# 3K_valdiklis_v1.net
KiCad netlist of a schematic drawn in EAGLE
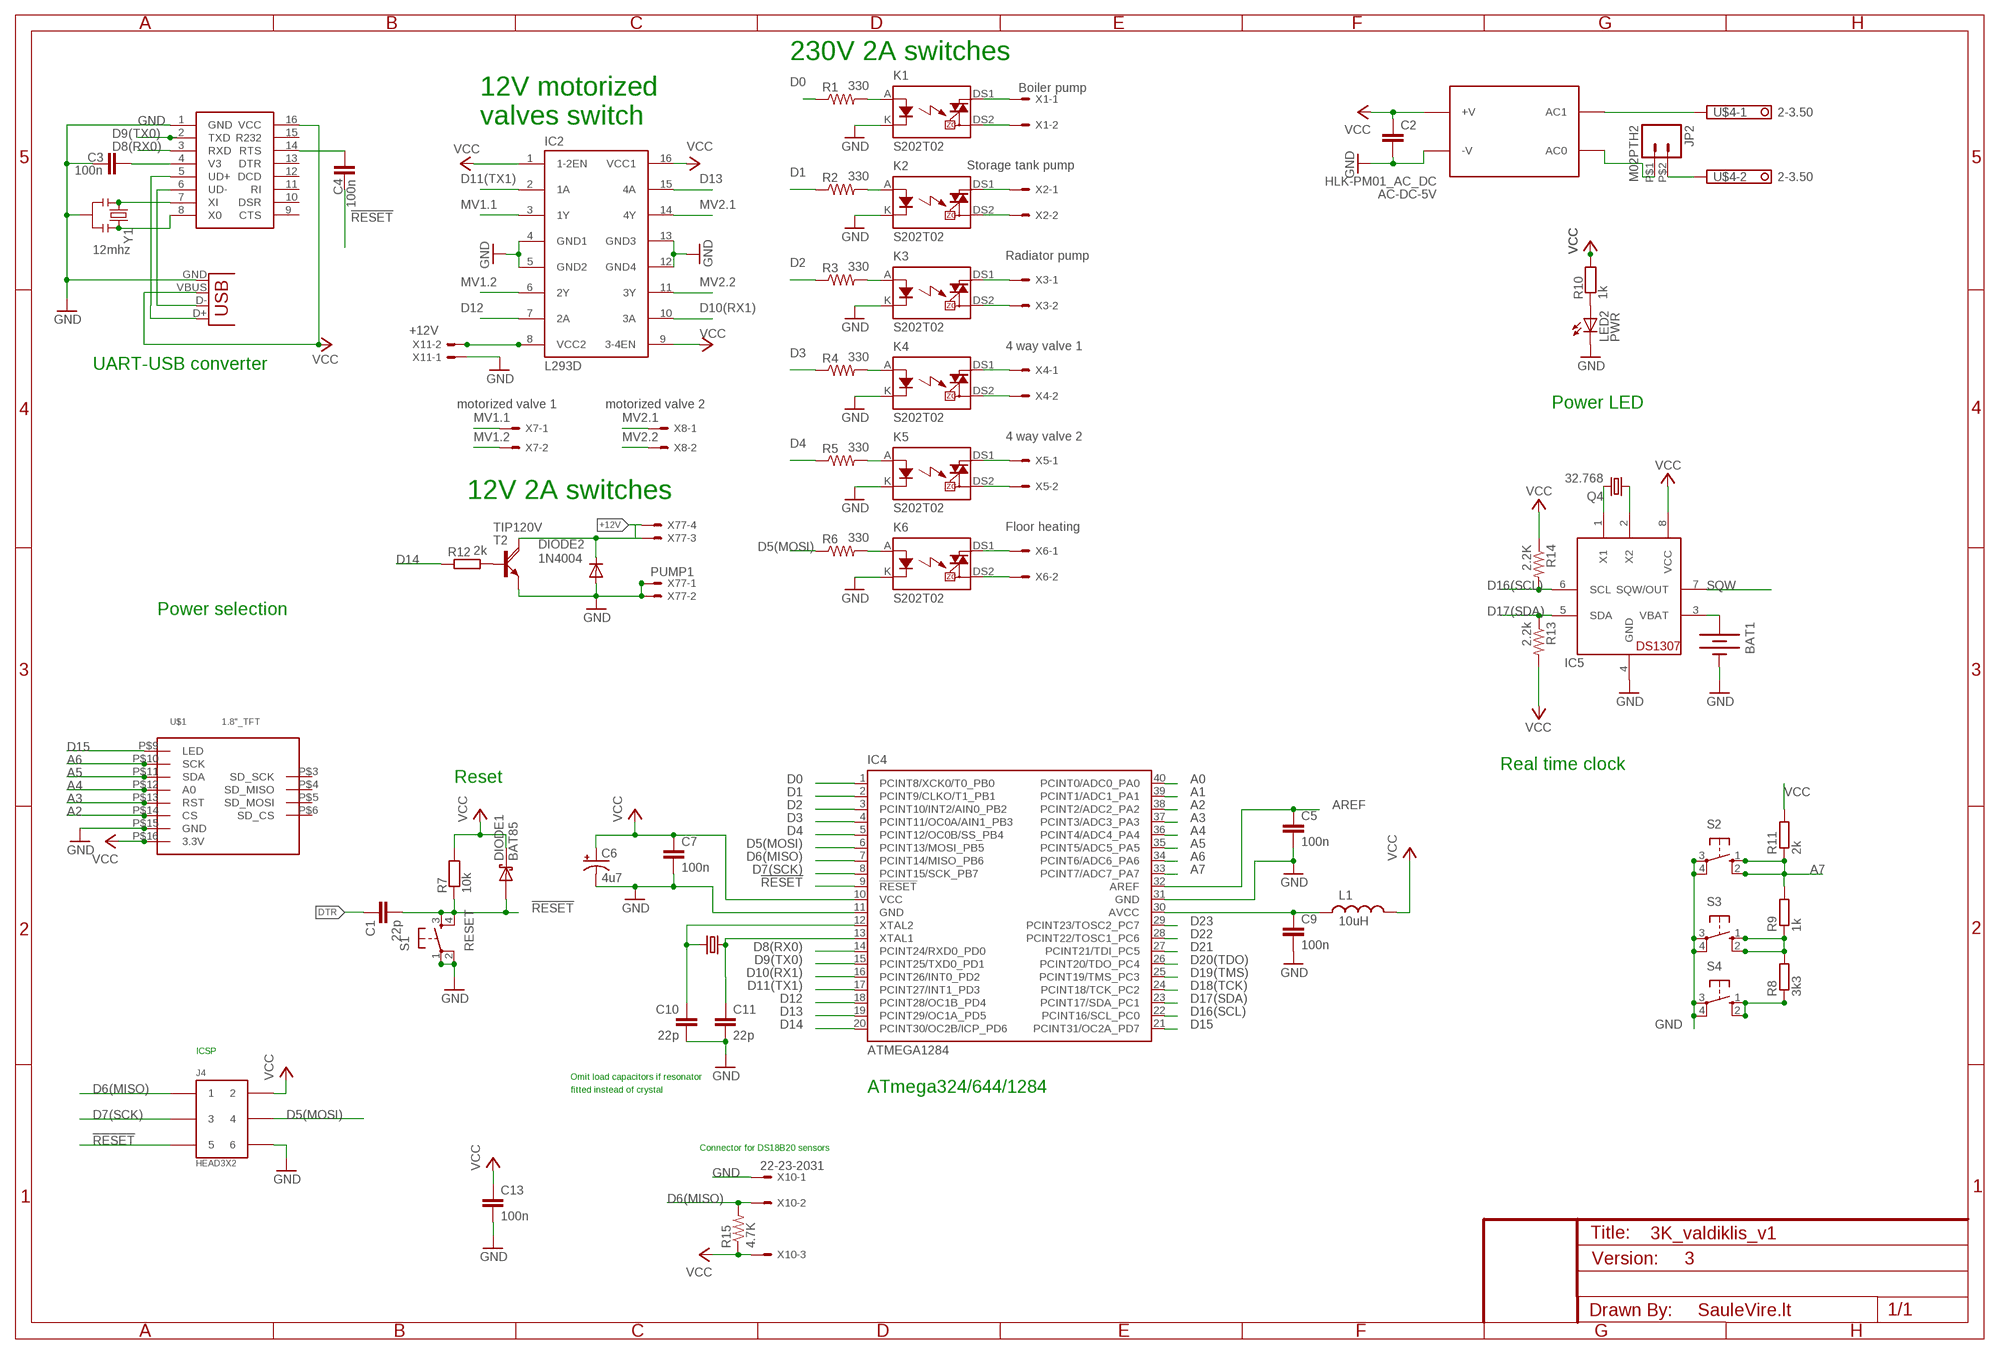
[diagram p0: schematic, sheet 1]

(export (version "E")
  (design (tool "Eeschema 10.0.6"))
  (components
    (comp (ref "AC-DC-5V")
      (value "HLK-PM01_AC_DC")
      (footprint "eagle-import:HLK-PM01_AC_DC")
      (libsource (lib "eagle-import") (part "HLK-PM01_AC_DC"))
    )
    (comp (ref "BAT1")
      (value "BATTERY20PTH")
      (footprint "eagle-import:BATTCOM_20MM_PTH")
      (libsource (lib "eagle-import") (part "BATTERY20PTH"))
    )
    (comp (ref "C1")
      (value "22p")
      (footprint "eagle-import:CAP-PTH-SMALL")
      (libsource (lib "eagle-import") (part "CAPPTH"))
    )
    (comp (ref "C2")
      (value "C-EU025-024X044")
      (footprint "eagle-import:C025-024X044")
      (libsource (lib "eagle-import") (part "C-EU025-024X044"))
    )
    (comp (ref "C3")
      (value "100n")
      (footprint "eagle-import:CAP-PTH-SMALL")
      (libsource (lib "eagle-import") (part "CAPPTH"))
    )
    (comp (ref "C4")
      (value "100n")
      (footprint "eagle-import:CAP-PTH-SMALL")
      (libsource (lib "eagle-import") (part "CAPPTH"))
    )
    (comp (ref "C5")
      (value "100n")
      (footprint "eagle-import:CAP-PTH-SMALL")
      (libsource (lib "eagle-import") (part "CAPPTH"))
    )
    (comp (ref "C6")
      (value "4u7")
      (footprint "eagle-import:CPOL-RADIAL-10UF-25V")
      (libsource (lib "eagle-import") (part "CAP_POLPTH2"))
    )
    (comp (ref "C7")
      (value "100n")
      (footprint "eagle-import:CAP-PTH-SMALL")
      (libsource (lib "eagle-import") (part "CAPPTH"))
    )
    (comp (ref "C9")
      (value "100n")
      (footprint "eagle-import:CAP-PTH-SMALL")
      (libsource (lib "eagle-import") (part "CAPPTH"))
    )
    (comp (ref "C10")
      (value "22p")
      (footprint "eagle-import:CAP-PTH-SMALL")
      (libsource (lib "eagle-import") (part "CAPPTH"))
    )
    (comp (ref "C11")
      (value "22p")
      (footprint "eagle-import:CAP-PTH-SMALL")
      (libsource (lib "eagle-import") (part "CAPPTH"))
    )
    (comp (ref "C13")
      (value "100n")
      (footprint "eagle-import:CAP-PTH-SMALL")
      (libsource (lib "eagle-import") (part "CAPPTH"))
    )
    (comp (ref "DIODE1")
      (value "BAT85")
      (footprint "eagle-import:DIODE-TH-0.4")
      (libsource (lib "eagle-import") (part "DIODE-SCHOTTKY"))
    )
    (comp (ref "DIODE2")
      (value "1N4004")
      (footprint "eagle-import:DO41-10")
      (libsource (lib "eagle-import") (part "1N4004"))
    )
    (comp (ref "IC2")
      (value "L293D")
      (footprint "eagle-import:DIL16")
      (libsource (lib "eagle-import") (part "L293D"))
    )
    (comp (ref "IC4")
      (value "ATMEGA1284")
      (footprint "eagle-import:DIL40")
      (fields (field (name "MPN") "ATMEGA644-20PU"))
      (libsource (lib "eagle-import") (part "ATMEGA644-PU20"))
    )
    (comp (ref "IC5")
      (value "DS1307")
      (footprint "eagle-import:DIL08")
      (libsource (lib "eagle-import") (part "DS1307"))
    )
    (comp (ref "J4")
      (value "HEAD3X2")
      (footprint "eagle-import:HEAD3X2")
      (libsource (lib "eagle-import") (part "HEAD3X2"))
    )
    (comp (ref "JP2")
      (value "M02PTH2")
      (footprint "eagle-import:1X02_BIG")
      (libsource (lib "eagle-import") (part "M02PTH2"))
    )
    (comp (ref "JP3")
      (value "USB-B")
      (footprint "eagle-import:USB-B-PTH")
      (libsource (lib "eagle-import") (part "USBPTH"))
    )
    (comp (ref "K1")
      (value "S202T02")
      (footprint "eagle-import:S202T02")
      (libsource (lib "eagle-import") (part "S202T02"))
    )
    (comp (ref "K2")
      (value "S202T02")
      (footprint "eagle-import:S202T02")
      (libsource (lib "eagle-import") (part "S202T02"))
    )
    (comp (ref "K3")
      (value "S202T02")
      (footprint "eagle-import:S202T02")
      (libsource (lib "eagle-import") (part "S202T02"))
    )
    (comp (ref "K4")
      (value "S202T02")
      (footprint "eagle-import:S202T02")
      (libsource (lib "eagle-import") (part "S202T02"))
    )
    (comp (ref "K5")
      (value "S202T02")
      (footprint "eagle-import:S202T02")
      (libsource (lib "eagle-import") (part "S202T02"))
    )
    (comp (ref "K6")
      (value "S202T02")
      (footprint "eagle-import:S202T02")
      (libsource (lib "eagle-import") (part "S202T02"))
    )
    (comp (ref "L1")
      (value "10uH")
      (footprint "eagle-import:RES-AXIAL-0.4")
      (libsource (lib "eagle-import") (part "INDUCTOR0.4{dblquote}-AXIAL"))
    )
    (comp (ref "LED2")
      (value "PWR")
      (footprint "eagle-import:LED3MM")
      (libsource (lib "eagle-import") (part "LED3MM"))
    )
    (comp (ref "Q4")
      (value "32.768")
      (footprint "eagle-import:TC38H")
      (libsource (lib "eagle-import") (part "CRYTALTC38H"))
    )
    (comp (ref "R1")
      (value "330")
      (footprint "eagle-import:0207_10")
      (libsource (lib "eagle-import") (part "resistor-1_R-US_0207/10"))
    )
    (comp (ref "R2")
      (value "330")
      (footprint "eagle-import:0207_10")
      (libsource (lib "eagle-import") (part "resistor-1_R-US_0207/10"))
    )
    (comp (ref "R3")
      (value "330")
      (footprint "eagle-import:0207_10")
      (libsource (lib "eagle-import") (part "resistor-1_R-US_0207/10"))
    )
    (comp (ref "R4")
      (value "330")
      (footprint "eagle-import:0207_10")
      (libsource (lib "eagle-import") (part "resistor-1_R-US_0207/10"))
    )
    (comp (ref "R5")
      (value "330")
      (footprint "eagle-import:0207_10")
      (libsource (lib "eagle-import") (part "resistor-1_R-US_0207/10"))
    )
    (comp (ref "R6")
      (value "330")
      (footprint "eagle-import:0207_10")
      (libsource (lib "eagle-import") (part "resistor-1_R-US_0207/10"))
    )
    (comp (ref "R7")
      (value "10k")
      (footprint "eagle-import:RES-AXIAL-0.4")
      (libsource (lib "eagle-import") (part "RESISTOR"))
    )
    (comp (ref "R8")
      (value "3k3")
      (footprint "eagle-import:0207_10")
      (libsource (lib "eagle-import") (part "R-EU_0207/10"))
    )
    (comp (ref "R9")
      (value "1k")
      (footprint "eagle-import:0207_10")
      (libsource (lib "eagle-import") (part "R-EU_0207/10"))
    )
    (comp (ref "R10")
      (value "1k")
      (footprint "eagle-import:RES-AXIAL-0.4")
      (libsource (lib "eagle-import") (part "RESISTOR"))
    )
    (comp (ref "R11")
      (value "2k")
      (footprint "eagle-import:0207_10")
      (libsource (lib "eagle-import") (part "R-EU_0207/10"))
    )
    (comp (ref "R12")
      (value "2k")
      (footprint "eagle-import:0207_10")
      (libsource (lib "eagle-import") (part "R-EU_0207/10"))
    )
    (comp (ref "R13")
      (value "2.2k")
      (footprint "eagle-import:0207_10")
      (libsource (lib "eagle-import") (part "R-US_0207/10"))
    )
    (comp (ref "R14")
      (value "2.2K")
      (footprint "eagle-import:0207_10")
      (libsource (lib "eagle-import") (part "R-US_0207/10"))
    )
    (comp (ref "R15")
      (value "4.7K")
      (footprint "eagle-import:0207_10")
      (libsource (lib "eagle-import") (part "R-US_0207/10"))
    )
    (comp (ref "S1")
      (value "RESET")
      (footprint "eagle-import:TACTILE-PTH")
      (libsource (lib "eagle-import") (part "TAC_SWITCHPTH"))
    )
    (comp (ref "S2")
      (value "10-XX")
      (footprint "eagle-import:B3F-10XX")
      (fields (field (name "MPN") "B3F-1000"))
      (libsource (lib "eagle-import") (part "10-XX"))
    )
    (comp (ref "S3")
      (value "10-XX")
      (footprint "eagle-import:B3F-10XX")
      (fields (field (name "MPN") "B3F-1000"))
      (libsource (lib "eagle-import") (part "10-XX"))
    )
    (comp (ref "S4")
      (value "10-XX")
      (footprint "eagle-import:B3F-10XX")
      (fields (field (name "MPN") "B3F-1000"))
      (libsource (lib "eagle-import") (part "10-XX"))
    )
    (comp (ref "T2")
      (value "TIP120V")
      (footprint "eagle-import:TO220AV")
      (libsource (lib "eagle-import") (part "TIP120V"))
    )
    (comp (ref "U$1")
      (value "1.8\"_TFT")
      (footprint "eagle-import:1.8__TFT")
      (libsource (lib "eagle-import") (part "1.8{dblquote}_TFT"))
    )
    (comp (ref "U$2")
      (value "CH340G")
      (footprint "eagle-import:SO016")
      (libsource (lib "eagle-import") (part "CH340G"))
    )
    (comp (ref "U$4")
      (value "2-3.50")
      (footprint "eagle-import:2-3.50")
      (libsource (lib "eagle-import") (part "2-3.50"))
    )
    (comp (ref "X1")
      (value "Boiler pump")
      (footprint "eagle-import:22-23-2021")
      (fields (field (name "MF") "MOLEX") (field (name "MPN") "22-23-2021"))
      (libsource (lib "eagle-import") (part "22-23-2021"))
    )
    (comp (ref "X2")
      (value "Storage tank pump")
      (footprint "eagle-import:22-23-2021")
      (fields (field (name "MF") "MOLEX") (field (name "MPN") "22-23-2021"))
      (libsource (lib "eagle-import") (part "22-23-2021"))
    )
    (comp (ref "X3")
      (value "Radiator pump")
      (footprint "eagle-import:22-23-2021")
      (fields (field (name "MF") "MOLEX") (field (name "MPN") "22-23-2021"))
      (libsource (lib "eagle-import") (part "22-23-2021"))
    )
    (comp (ref "X4")
      (value "4 way valve 1")
      (footprint "eagle-import:22-23-2021")
      (fields (field (name "MF") "MOLEX") (field (name "MPN") "22-23-2021"))
      (libsource (lib "eagle-import") (part "22-23-2021"))
    )
    (comp (ref "X5")
      (value "4 way valve 2")
      (footprint "eagle-import:22-23-2021")
      (fields (field (name "MF") "MOLEX") (field (name "MPN") "22-23-2021"))
      (libsource (lib "eagle-import") (part "22-23-2021"))
    )
    (comp (ref "X6")
      (value "Floor heating")
      (footprint "eagle-import:22-23-2021")
      (fields (field (name "MF") "MOLEX") (field (name "MPN") "22-23-2021"))
      (libsource (lib "eagle-import") (part "22-23-2021"))
    )
    (comp (ref "X7")
      (value "motorized valve 1")
      (footprint "eagle-import:22-23-2021")
      (fields (field (name "MF") "MOLEX") (field (name "MPN") "22-23-2021"))
      (libsource (lib "eagle-import") (part "22-23-2021"))
    )
    (comp (ref "X8")
      (value "motorized valve 2")
      (footprint "eagle-import:22-23-2021")
      (fields (field (name "MF") "MOLEX") (field (name "MPN") "22-23-2021"))
      (libsource (lib "eagle-import") (part "22-23-2021"))
    )
    (comp (ref "X9")
      (value "16MHz")
      (footprint "eagle-import:HC49US")
      (libsource (lib "eagle-import") (part "CRYSTALHC49US"))
    )
    (comp (ref "X10")
      (value "22-23-2031")
      (footprint "eagle-import:22-23-2031")
      (fields (field (name "MF") "MOLEX"))
      (libsource (lib "eagle-import") (part "22-23-2031"))
    )
    (comp (ref "X11")
      (value "+12V")
      (footprint "eagle-import:22-23-2021")
      (fields (field (name "MF") "MOLEX") (field (name "MPN") "22-23-2021"))
      (libsource (lib "eagle-import") (part "22-23-2021"))
    )
    (comp (ref "X77")
      (value "PUMP1")
      (footprint "eagle-import:22-23-2041")
      (fields (field (name "MF") "MOLEX") (field (name "MPN") "22-23-2041"))
      (libsource (lib "eagle-import") (part "22-23-2041"))
    )
    (comp (ref "Y1")
      (value "12mhz")
      (footprint "eagle-import:RESONATOR-PTH")
      (libsource (lib "eagle-import") (part "RESONATORPTH"))
    )
  )
  (nets
    (net (code "1") (name "+12V") (class "Default")
      (node (ref "DIODE2") (pin "C") (pinfunction "C_C") (pintype "passive"))
      (node (ref "T2") (pin "C") (pinfunction "C_C") (pintype "passive"))
      (node (ref "X77") (pin "3") (pinfunction "S_3") (pintype "passive"))
      (node (ref "X77") (pin "4") (pinfunction "S_4") (pintype "passive"))
    )
    (net (code "2") (name "/A0") (class "Default")
      (node (ref "IC4") (pin "40") (pinfunction "PCINT0/ADC0_PA0_40") (pintype "bidirectional"))
    )
    (net (code "3") (name "/A1") (class "Default")
      (node (ref "IC4") (pin "39") (pinfunction "PCINT1/ADC1_PA1_39") (pintype "bidirectional"))
    )
    (net (code "4") (name "/A2") (class "Default")
      (node (ref "IC4") (pin "38") (pinfunction "PCINT2/ADC2_PA2_38") (pintype "bidirectional"))
      (node (ref "U$1") (pin "P$14") (pinfunction "CS_P$14") (pintype "bidirectional"))
    )
    (net (code "5") (name "/A3") (class "Default")
      (node (ref "IC4") (pin "37") (pinfunction "PCINT3/ADC3_PA3_37") (pintype "bidirectional"))
      (node (ref "U$1") (pin "P$13") (pinfunction "RST_P$13") (pintype "bidirectional"))
    )
    (net (code "6") (name "/A4") (class "Default")
      (node (ref "IC4") (pin "36") (pinfunction "PCINT4/ADC4_PA4_36") (pintype "bidirectional"))
      (node (ref "U$1") (pin "P$12") (pinfunction "A0_P$12") (pintype "bidirectional"))
    )
    (net (code "7") (name "/A5") (class "Default")
      (node (ref "IC4") (pin "35") (pinfunction "PCINT5/ADC5_PA5_35") (pintype "bidirectional"))
      (node (ref "U$1") (pin "P$11") (pinfunction "SDA_P$11") (pintype "bidirectional"))
    )
    (net (code "8") (name "/A6") (class "Default")
      (node (ref "IC4") (pin "34") (pinfunction "PCINT6/ADC6_PA6_34") (pintype "bidirectional"))
      (node (ref "U$1") (pin "P$10") (pinfunction "SCK_P$10") (pintype "bidirectional"))
    )
    (net (code "9") (name "/A7") (class "Default")
      (node (ref "IC4") (pin "33") (pinfunction "PCINT7/ADC7_PA7_33") (pintype "bidirectional"))
      (node (ref "R11") (pin "1") (pinfunction "1_1") (pintype "passive"))
      (node (ref "R9") (pin "2") (pinfunction "2_2") (pintype "passive"))
      (node (ref "S2") (pin "1") (pinfunction "S_1") (pintype "passive"))
      (node (ref "S2") (pin "2") (pinfunction "S1_2") (pintype "passive"))
    )
    (net (code "10") (name "/AREF") (class "Default")
      (node (ref "C5") (pin "1") (pinfunction "1_1") (pintype "passive"))
      (node (ref "IC4") (pin "32") (pinfunction "AREF_32") (pintype "passive"))
    )
    (net (code "11") (name "/D0") (class "Default")
      (node (ref "IC4") (pin "1") (pinfunction "PCINT8/XCK0/T0_PB0_1") (pintype "bidirectional"))
      (node (ref "R1") (pin "1") (pinfunction "1_1") (pintype "passive"))
    )
    (net (code "12") (name "/D1") (class "Default")
      (node (ref "IC4") (pin "2") (pinfunction "PCINT9/CLKO/T1_PB1_2") (pintype "bidirectional"))
      (node (ref "R2") (pin "1") (pinfunction "1_1") (pintype "passive"))
    )
    (net (code "13") (name "/D2") (class "Default")
      (node (ref "IC4") (pin "3") (pinfunction "PCINT10/INT2/AIN0_PB2_3") (pintype "bidirectional"))
      (node (ref "R3") (pin "1") (pinfunction "1_1") (pintype "passive"))
    )
    (net (code "14") (name "/D3") (class "Default")
      (node (ref "IC4") (pin "4") (pinfunction "PCINT11/OC0A/AIN1_PB3_4") (pintype "bidirectional"))
      (node (ref "R4") (pin "1") (pinfunction "1_1") (pintype "passive"))
    )
    (net (code "15") (name "/D4") (class "Default")
      (node (ref "IC4") (pin "5") (pinfunction "PCINT12/OC0B/SS_PB4_5") (pintype "bidirectional"))
      (node (ref "R5") (pin "1") (pinfunction "1_1") (pintype "passive"))
    )
    (net (code "16") (name "/D5(MOSI)") (class "Default")
      (node (ref "IC4") (pin "6") (pinfunction "PCINT13/MOSI_PB5_6") (pintype "bidirectional"))
      (node (ref "J4") (pin "4") (pinfunction "4_4") (pintype "passive"))
      (node (ref "R6") (pin "1") (pinfunction "1_1") (pintype "passive"))
    )
    (net (code "17") (name "/D6(MISO)") (class "Default")
      (node (ref "IC4") (pin "7") (pinfunction "PCINT14/MISO_PB6_7") (pintype "bidirectional"))
      (node (ref "J4") (pin "1") (pinfunction "1_1") (pintype "passive"))
      (node (ref "R15") (pin "2") (pinfunction "2_2") (pintype "passive"))
      (node (ref "X10") (pin "2") (pinfunction "S_2") (pintype "passive"))
    )
    (net (code "18") (name "/D7(SCK)") (class "Default")
      (node (ref "IC4") (pin "8") (pinfunction "PCINT15/SCK_PB7_8") (pintype "bidirectional"))
      (node (ref "J4") (pin "3") (pinfunction "3_3") (pintype "passive"))
    )
    (net (code "19") (name "/D8(RX0)") (class "Default")
      (node (ref "IC4") (pin "14") (pinfunction "PCINT24/RXD0_PD0_14") (pintype "bidirectional"))
      (node (ref "U$2") (pin "3") (pinfunction "RXD_3") (pintype "bidirectional"))
    )
    (net (code "20") (name "/D9(TX0)") (class "Default")
      (node (ref "IC4") (pin "15") (pinfunction "PCINT25/TXD0_PD1_15") (pintype "bidirectional"))
      (node (ref "U$2") (pin "2") (pinfunction "TXD_2") (pintype "bidirectional"))
    )
    (net (code "21") (name "/D10(RX1)") (class "Default")
      (node (ref "IC2") (pin "10") (pinfunction "3A_10") (pintype "input"))
      (node (ref "IC4") (pin "16") (pinfunction "PCINT26/INT0_PD2_16") (pintype "bidirectional"))
    )
    (net (code "22") (name "/D11(TX1)") (class "Default")
      (node (ref "IC2") (pin "2") (pinfunction "1A_2") (pintype "input"))
      (node (ref "IC4") (pin "17") (pinfunction "PCINT27/INT1_PD3_17") (pintype "bidirectional"))
    )
    (net (code "23") (name "/D12") (class "Default")
      (node (ref "IC2") (pin "7") (pinfunction "2A_7") (pintype "input"))
      (node (ref "IC4") (pin "18") (pinfunction "PCINT28/OC1B_PD4_18") (pintype "bidirectional"))
    )
    (net (code "24") (name "/D13") (class "Default")
      (node (ref "IC2") (pin "15") (pinfunction "4A_15") (pintype "input"))
      (node (ref "IC4") (pin "19") (pinfunction "PCINT29/OC1A_PD5_19") (pintype "bidirectional"))
    )
    (net (code "25") (name "/D14") (class "Default")
      (node (ref "IC4") (pin "20") (pinfunction "PCINT30/OC2B/ICP_PD6_20") (pintype "bidirectional"))
      (node (ref "R12") (pin "1") (pinfunction "1_1") (pintype "passive"))
    )
    (net (code "26") (name "/D15") (class "Default")
      (node (ref "IC4") (pin "21") (pinfunction "PCINT31/OC2A_PD7_21") (pintype "bidirectional"))
      (node (ref "U$1") (pin "P$9") (pinfunction "LED_P$9") (pintype "bidirectional"))
    )
    (net (code "27") (name "/D16(SCL)") (class "Default")
      (node (ref "IC4") (pin "22") (pinfunction "PCINT16/SCL_PC0_22") (pintype "bidirectional"))
      (node (ref "IC5") (pin "6") (pinfunction "SCL_6") (pintype "bidirectional"))
      (node (ref "R14") (pin "2") (pinfunction "2_2") (pintype "passive"))
    )
    (net (code "28") (name "/D17(SDA)") (class "Default")
      (node (ref "IC4") (pin "23") (pinfunction "PCINT17/SDA_PC1_23") (pintype "bidirectional"))
      (node (ref "IC5") (pin "5") (pinfunction "SDA_5") (pintype "bidirectional"))
      (node (ref "R13") (pin "1") (pinfunction "1_1") (pintype "passive"))
    )
    (net (code "29") (name "/D18(TCK)") (class "Default")
      (node (ref "IC4") (pin "24") (pinfunction "PCINT18/TCK_PC2_24") (pintype "bidirectional"))
    )
    (net (code "30") (name "/D19(TMS)") (class "Default")
      (node (ref "IC4") (pin "25") (pinfunction "PCINT19/TMS_PC3_25") (pintype "bidirectional"))
    )
    (net (code "31") (name "/D20(TDO)") (class "Default")
      (node (ref "IC4") (pin "26") (pinfunction "PCINT20/TDO_PC4_26") (pintype "bidirectional"))
    )
    (net (code "32") (name "/D21") (class "Default")
      (node (ref "IC4") (pin "27") (pinfunction "PCINT21/TDI_PC5_27") (pintype "bidirectional"))
    )
    (net (code "33") (name "/D22") (class "Default")
      (node (ref "IC4") (pin "28") (pinfunction "PCINT22/TOSC1_PC6_28") (pintype "bidirectional"))
    )
    (net (code "34") (name "/D23") (class "Default")
      (node (ref "IC4") (pin "29") (pinfunction "PCINT23/TOSC2_PC7_29") (pintype "bidirectional"))
    )
    (net (code "35") (name "/MV1.1") (class "Default")
      (node (ref "IC2") (pin "3") (pinfunction "1Y_3") (pintype "output"))
      (node (ref "X7") (pin "1") (pinfunction "S_1") (pintype "passive"))
    )
    (net (code "36") (name "/MV1.2") (class "Default")
      (node (ref "IC2") (pin "6") (pinfunction "2Y_6") (pintype "output"))
      (node (ref "X7") (pin "2") (pinfunction "S_2") (pintype "passive"))
    )
    (net (code "37") (name "/MV2.1") (class "Default")
      (node (ref "IC2") (pin "14") (pinfunction "4Y_14") (pintype "output"))
      (node (ref "X8") (pin "1") (pinfunction "S_1") (pintype "passive"))
    )
    (net (code "38") (name "/MV2.2") (class "Default")
      (node (ref "IC2") (pin "11") (pinfunction "3Y_11") (pintype "output"))
      (node (ref "X8") (pin "2") (pinfunction "S_2") (pintype "passive"))
    )
    (net (code "39") (name "/SQW") (class "Default")
      (node (ref "IC5") (pin "7") (pinfunction "SQW/OUT_7") (pintype "bidirectional"))
    )
    (net (code "40") (name "/~{RESET}") (class "Default")
      (node (ref "C1") (pin "2") (pinfunction "2_2") (pintype "passive"))
      (node (ref "C4") (pin "1") (pinfunction "1_1") (pintype "passive"))
      (node (ref "DIODE1") (pin "A") (pinfunction "A_A") (pintype "passive"))
      (node (ref "IC4") (pin "9") (pinfunction "~{RESET}_9") (pintype "input"))
      (node (ref "J4") (pin "5") (pinfunction "5_5") (pintype "passive"))
      (node (ref "R7") (pin "P$1") (pinfunction "1_P$1") (pintype "passive"))
      (node (ref "S1") (pin "3") (pinfunction "3_3") (pintype "passive"))
      (node (ref "S1") (pin "4") (pinfunction "4_4") (pintype "passive"))
    )
    (net (code "41") (name "DTR") (class "Default")
      (node (ref "C1") (pin "1") (pinfunction "1_1") (pintype "passive"))
    )
    (net (code "42") (name "GND") (class "Default")
      (node (ref "AC-DC-5V") (pin "-V") (pinfunction "-V_-V") (pintype "output"))
      (node (ref "BAT1") (pin "2") (pinfunction "-_2") (pintype "power_in"))
      (node (ref "C10") (pin "2") (pinfunction "2_2") (pintype "passive"))
      (node (ref "C11") (pin "2") (pinfunction "2_2") (pintype "passive"))
      (node (ref "C13") (pin "2") (pinfunction "2_2") (pintype "passive"))
      (node (ref "C2") (pin "2") (pinfunction "2_2") (pintype "passive"))
      (node (ref "C3") (pin "1") (pinfunction "1_1") (pintype "passive"))
      (node (ref "C5") (pin "2") (pinfunction "2_2") (pintype "passive"))
      (node (ref "C6") (pin "2") (pinfunction "-_2") (pintype "passive"))
      (node (ref "C7") (pin "2") (pinfunction "2_2") (pintype "passive"))
      (node (ref "C9") (pin "2") (pinfunction "2_2") (pintype "passive"))
      (node (ref "DIODE2") (pin "A") (pinfunction "A_A") (pintype "passive"))
      (node (ref "IC2") (pin "12") (pinfunction "GND4_12") (pintype "power_in"))
      (node (ref "IC2") (pin "13") (pinfunction "GND3_13") (pintype "power_in"))
      (node (ref "IC2") (pin "4") (pinfunction "GND1_4") (pintype "power_in"))
      (node (ref "IC2") (pin "5") (pinfunction "GND2_5") (pintype "power_in"))
      (node (ref "IC4") (pin "11") (pinfunction "GND_11") (pintype "power_in"))
      (node (ref "IC4") (pin "31") (pinfunction "GND_31") (pintype "power_in"))
      (node (ref "IC5") (pin "4") (pinfunction "GND_4") (pintype "power_in"))
      (node (ref "J4") (pin "6") (pinfunction "6_6") (pintype "passive"))
      (node (ref "JP3") (pin "GND") (pinfunction "GND_GND") (pintype "bidirectional"))
      (node (ref "K1") (pin "K") (pinfunction "K_K") (pintype "passive"))
      (node (ref "K2") (pin "K") (pinfunction "K_K") (pintype "passive"))
      (node (ref "K3") (pin "K") (pinfunction "K_K") (pintype "passive"))
      (node (ref "K4") (pin "K") (pinfunction "K_K") (pintype "passive"))
      (node (ref "K5") (pin "K") (pinfunction "K_K") (pintype "passive"))
      (node (ref "K6") (pin "K") (pinfunction "K_K") (pintype "passive"))
      (node (ref "LED2") (pin "K") (pinfunction "C_K") (pintype "passive"))
      (node (ref "S1") (pin "1") (pinfunction "1_1") (pintype "passive"))
      (node (ref "S1") (pin "2") (pinfunction "2_2") (pintype "passive"))
      (node (ref "S2") (pin "3") (pinfunction "P_3") (pintype "passive"))
      (node (ref "S2") (pin "4") (pinfunction "P1_4") (pintype "passive"))
      (node (ref "S3") (pin "3") (pinfunction "P_3") (pintype "passive"))
      (node (ref "S3") (pin "4") (pinfunction "P1_4") (pintype "passive"))
      (node (ref "S4") (pin "3") (pinfunction "P_3") (pintype "passive"))
      (node (ref "S4") (pin "4") (pinfunction "P1_4") (pintype "passive"))
      (node (ref "T2") (pin "E") (pinfunction "E_E") (pintype "passive"))
      (node (ref "U$1") (pin "P$15") (pinfunction "GND_P$15") (pintype "bidirectional"))
      (node (ref "U$2") (pin "1") (pinfunction "GND_1") (pintype "bidirectional"))
      (node (ref "X10") (pin "1") (pinfunction "S_1") (pintype "passive"))
      (node (ref "X11") (pin "1") (pinfunction "S_1") (pintype "passive"))
      (node (ref "X77") (pin "1") (pinfunction "S_1") (pintype "passive"))
      (node (ref "X77") (pin "2") (pinfunction "S_2") (pintype "passive"))
      (node (ref "Y1") (pin "2") (pinfunction "2_2") (pintype "passive"))
    )
    (net (code "43") (name "Net-(BAT1-+)") (class "Default")
      (node (ref "BAT1") (pin "1") (pinfunction "+_1") (pintype "power_in"))
      (node (ref "IC5") (pin "3") (pinfunction "VBAT_3") (pintype "power_in"))
    )
    (net (code "44") (name "Net-(IC2-VCC2)") (class "Default")
      (node (ref "IC2") (pin "8") (pinfunction "VCC2_8") (pintype "power_in"))
      (node (ref "X11") (pin "2") (pinfunction "S_2") (pintype "passive"))
    )
    (net (code "45") (name "Net-(IC4-AVCC)") (class "Default")
      (node (ref "C9") (pin "1") (pinfunction "1_1") (pintype "passive"))
      (node (ref "IC4") (pin "30") (pinfunction "AVCC_30") (pintype "power_in"))
      (node (ref "L1") (pin "P$1") (pinfunction "1_P$1") (pintype "passive"))
    )
    (net (code "46") (name "Net-(IC4-XTAL1)") (class "Default")
      (node (ref "C11") (pin "1") (pinfunction "1_1") (pintype "passive"))
      (node (ref "IC4") (pin "13") (pinfunction "XTAL1_13") (pintype "input"))
      (node (ref "X9") (pin "1") (pinfunction "1_1") (pintype "passive"))
    )
    (net (code "47") (name "Net-(IC4-XTAL2)") (class "Default")
      (node (ref "C10") (pin "1") (pinfunction "1_1") (pintype "passive"))
      (node (ref "IC4") (pin "12") (pinfunction "XTAL2_12") (pintype "output"))
      (node (ref "X9") (pin "2") (pinfunction "2_2") (pintype "passive"))
    )
    (net (code "48") (name "Net-(IC5-X1)") (class "Default")
      (node (ref "IC5") (pin "1") (pinfunction "X1_1") (pintype "passive"))
      (node (ref "Q4") (pin "2") (pinfunction "2_2") (pintype "passive"))
    )
    (net (code "49") (name "Net-(IC5-X2)") (class "Default")
      (node (ref "IC5") (pin "2") (pinfunction "X2_2") (pintype "passive"))
      (node (ref "Q4") (pin "1") (pinfunction "1_1") (pintype "passive"))
    )
    (net (code "50") (name "Net-(JP2-1)") (class "Default")
      (node (ref "AC-DC-5V") (pin "AC0") (pinfunction "AC0_AC0") (pintype "power_in"))
      (node (ref "JP2") (pin "P$1") (pinfunction "1_P$1") (pintype "passive"))
    )
    (net (code "51") (name "Net-(JP2-2)") (class "Default")
      (node (ref "JP2") (pin "P$2") (pinfunction "2_P$2") (pintype "passive"))
      (node (ref "U$4") (pin "2") (pinfunction "K_2") (pintype "passive"))
    )
    (net (code "52") (name "Net-(K1-PadA)") (class "Default")
      (node (ref "K1") (pin "A") (pinfunction "A_A") (pintype "passive"))
      (node (ref "R1") (pin "2") (pinfunction "2_2") (pintype "passive"))
    )
    (net (code "53") (name "Net-(K2-PadA)") (class "Default")
      (node (ref "K2") (pin "A") (pinfunction "A_A") (pintype "passive"))
      (node (ref "R2") (pin "2") (pinfunction "2_2") (pintype "passive"))
    )
    (net (code "54") (name "Net-(K3-PadA)") (class "Default")
      (node (ref "K3") (pin "A") (pinfunction "A_A") (pintype "passive"))
      (node (ref "R3") (pin "2") (pinfunction "2_2") (pintype "passive"))
    )
    (net (code "55") (name "Net-(K4-PadA)") (class "Default")
      (node (ref "K4") (pin "A") (pinfunction "A_A") (pintype "passive"))
      (node (ref "R4") (pin "2") (pinfunction "2_2") (pintype "passive"))
    )
    (net (code "56") (name "Net-(K5-PadA)") (class "Default")
      (node (ref "K5") (pin "A") (pinfunction "A_A") (pintype "passive"))
      (node (ref "R5") (pin "2") (pinfunction "2_2") (pintype "passive"))
    )
    (net (code "57") (name "Net-(K6-PadA)") (class "Default")
      (node (ref "K6") (pin "A") (pinfunction "A_A") (pintype "passive"))
      (node (ref "R6") (pin "2") (pinfunction "2_2") (pintype "passive"))
    )
    (net (code "58") (name "Net-(R10-1)") (class "Default")
      (node (ref "LED2") (pin "A") (pinfunction "A_A") (pintype "passive"))
      (node (ref "R10") (pin "P$1") (pinfunction "1_P$1") (pintype "passive"))
    )
    (net (code "59") (name "Net-(R12-Pad2)") (class "Default")
      (node (ref "R12") (pin "2") (pinfunction "2_2") (pintype "passive"))
      (node (ref "T2") (pin "B") (pinfunction "B_B") (pintype "passive"))
    )
    (net (code "60") (name "Net-(S3-S)") (class "Default")
      (node (ref "R8") (pin "2") (pinfunction "2_2") (pintype "passive"))
      (node (ref "R9") (pin "1") (pinfunction "1_1") (pintype "passive"))
      (node (ref "S3") (pin "1") (pinfunction "S_1") (pintype "passive"))
      (node (ref "S3") (pin "2") (pinfunction "S1_2") (pintype "passive"))
    )
    (net (code "61") (name "Net-(S4-S)") (class "Default")
      (node (ref "R8") (pin "1") (pinfunction "1_1") (pintype "passive"))
      (node (ref "S4") (pin "1") (pinfunction "S_1") (pintype "passive"))
      (node (ref "S4") (pin "2") (pinfunction "S1_2") (pintype "passive"))
    )
    (net (code "62") (name "Net-(U$2-RTS)") (class "Default")
      (node (ref "C4") (pin "2") (pinfunction "2_2") (pintype "passive"))
      (node (ref "U$2") (pin "14") (pinfunction "RTS_14") (pintype "bidirectional"))
    )
    (net (code "63") (name "Net-(U$2-UD+)") (class "Default")
      (node (ref "JP3") (pin "D+") (pinfunction "D+_D+") (pintype "bidirectional"))
      (node (ref "U$2") (pin "5") (pinfunction "UD+_5") (pintype "bidirectional"))
    )
    (net (code "64") (name "Net-(U$2-UD-)") (class "Default")
      (node (ref "JP3") (pin "D-") (pinfunction "D-_D-") (pintype "bidirectional"))
      (node (ref "U$2") (pin "6") (pinfunction "UD-_6") (pintype "bidirectional"))
    )
    (net (code "65") (name "Net-(U$2-V3)") (class "Default")
      (node (ref "C3") (pin "2") (pinfunction "2_2") (pintype "passive"))
      (node (ref "U$2") (pin "4") (pinfunction "V3_4") (pintype "bidirectional"))
    )
    (net (code "66") (name "Net-(U$2-X0)") (class "Default")
      (node (ref "U$2") (pin "8") (pinfunction "X0_8") (pintype "bidirectional"))
      (node (ref "Y1") (pin "3") (pinfunction "3_3") (pintype "passive"))
    )
    (net (code "67") (name "Net-(U$2-XI)") (class "Default")
      (node (ref "U$2") (pin "7") (pinfunction "XI_7") (pintype "bidirectional"))
      (node (ref "Y1") (pin "1") (pinfunction "1_1") (pintype "passive"))
    )
    (net (code "68") (name "Net-(U$4A-K)") (class "Default")
      (node (ref "AC-DC-5V") (pin "AC1") (pinfunction "AC1_AC1") (pintype "power_in"))
      (node (ref "U$4") (pin "1") (pinfunction "K_1") (pintype "passive"))
    )
    (net (code "69") (name "Net-(X1A-S)") (class "Default")
      (node (ref "K1") (pin "DS1") (pinfunction "DS1_DS1") (pintype "passive"))
      (node (ref "X1") (pin "1") (pinfunction "S_1") (pintype "passive"))
    )
    (net (code "70") (name "Net-(X1B-S)") (class "Default")
      (node (ref "K1") (pin "DS2") (pinfunction "DS2_DS2") (pintype "passive"))
      (node (ref "X1") (pin "2") (pinfunction "S_2") (pintype "passive"))
    )
    (net (code "71") (name "Net-(X2A-S)") (class "Default")
      (node (ref "K2") (pin "DS1") (pinfunction "DS1_DS1") (pintype "passive"))
      (node (ref "X2") (pin "1") (pinfunction "S_1") (pintype "passive"))
    )
    (net (code "72") (name "Net-(X2B-S)") (class "Default")
      (node (ref "K2") (pin "DS2") (pinfunction "DS2_DS2") (pintype "passive"))
      (node (ref "X2") (pin "2") (pinfunction "S_2") (pintype "passive"))
    )
    (net (code "73") (name "Net-(X3A-S)") (class "Default")
      (node (ref "K3") (pin "DS1") (pinfunction "DS1_DS1") (pintype "passive"))
      (node (ref "X3") (pin "1") (pinfunction "S_1") (pintype "passive"))
    )
    (net (code "74") (name "Net-(X3B-S)") (class "Default")
      (node (ref "K3") (pin "DS2") (pinfunction "DS2_DS2") (pintype "passive"))
      (node (ref "X3") (pin "2") (pinfunction "S_2") (pintype "passive"))
    )
    (net (code "75") (name "Net-(X4A-S)") (class "Default")
      (node (ref "K4") (pin "DS1") (pinfunction "DS1_DS1") (pintype "passive"))
      (node (ref "X4") (pin "1") (pinfunction "S_1") (pintype "passive"))
    )
    (net (code "76") (name "Net-(X4B-S)") (class "Default")
      (node (ref "K4") (pin "DS2") (pinfunction "DS2_DS2") (pintype "passive"))
      (node (ref "X4") (pin "2") (pinfunction "S_2") (pintype "passive"))
    )
    (net (code "77") (name "Net-(X5A-S)") (class "Default")
      (node (ref "K5") (pin "DS1") (pinfunction "DS1_DS1") (pintype "passive"))
      (node (ref "X5") (pin "1") (pinfunction "S_1") (pintype "passive"))
    )
    (net (code "78") (name "Net-(X5B-S)") (class "Default")
      (node (ref "K5") (pin "DS2") (pinfunction "DS2_DS2") (pintype "passive"))
      (node (ref "X5") (pin "2") (pinfunction "S_2") (pintype "passive"))
    )
    (net (code "79") (name "Net-(X6A-S)") (class "Default")
      (node (ref "K6") (pin "DS1") (pinfunction "DS1_DS1") (pintype "passive"))
      (node (ref "X6") (pin "1") (pinfunction "S_1") (pintype "passive"))
    )
    (net (code "80") (name "Net-(X6B-S)") (class "Default")
      (node (ref "K6") (pin "DS2") (pinfunction "DS2_DS2") (pintype "passive"))
      (node (ref "X6") (pin "2") (pinfunction "S_2") (pintype "passive"))
    )
    (net (code "81") (name "VCC") (class "Default")
      (node (ref "AC-DC-5V") (pin "+V") (pinfunction "+V_+V") (pintype "output"))
      (node (ref "C13") (pin "1") (pinfunction "1_1") (pintype "passive"))
      (node (ref "C2") (pin "1") (pinfunction "1_1") (pintype "passive"))
      (node (ref "C6") (pin "1") (pinfunction "+_1") (pintype "passive"))
      (node (ref "C7") (pin "1") (pinfunction "1_1") (pintype "passive"))
      (node (ref "DIODE1") (pin "C") (pinfunction "C_C") (pintype "passive"))
      (node (ref "IC2") (pin "1") (pinfunction "1-2EN_1") (pintype "input"))
      (node (ref "IC2") (pin "16") (pinfunction "VCC1_16") (pintype "power_in"))
      (node (ref "IC2") (pin "9") (pinfunction "3-4EN_9") (pintype "input"))
      (node (ref "IC4") (pin "10") (pinfunction "VCC_10") (pintype "power_in"))
      (node (ref "IC5") (pin "8") (pinfunction "VCC_8") (pintype "power_in"))
      (node (ref "J4") (pin "2") (pinfunction "2_2") (pintype "passive"))
      (node (ref "JP3") (pin "VBUS") (pinfunction "VBUS_VBUS") (pintype "bidirectional"))
      (node (ref "L1") (pin "P$2") (pinfunction "2_P$2") (pintype "passive"))
      (node (ref "R10") (pin "P$2") (pinfunction "2_P$2") (pintype "passive"))
      (node (ref "R11") (pin "2") (pinfunction "2_2") (pintype "passive"))
      (node (ref "R13") (pin "2") (pinfunction "2_2") (pintype "passive"))
      (node (ref "R14") (pin "1") (pinfunction "1_1") (pintype "passive"))
      (node (ref "R15") (pin "1") (pinfunction "1_1") (pintype "passive"))
      (node (ref "R7") (pin "P$2") (pinfunction "2_P$2") (pintype "passive"))
      (node (ref "U$1") (pin "P$16") (pinfunction "3.3V_P$16") (pintype "bidirectional"))
      (node (ref "U$2") (pin "16") (pinfunction "VCC_16") (pintype "bidirectional"))
      (node (ref "X10") (pin "3") (pinfunction "S_3") (pintype "passive"))
    )
    (net (code "82") (name "unconnected-(U$1-SD_CS-PadP$6)") (class "Default")
      (node (ref "U$1") (pin "P$6") (pinfunction "SD_CS_P$6") (pintype "bidirectional"))
    )
    (net (code "83") (name "unconnected-(U$1-SD_MISO-PadP$4)") (class "Default")
      (node (ref "U$1") (pin "P$4") (pinfunction "SD_MISO_P$4") (pintype "bidirectional"))
    )
    (net (code "84") (name "unconnected-(U$1-SD_MOSI-PadP$5)") (class "Default")
      (node (ref "U$1") (pin "P$5") (pinfunction "SD_MOSI_P$5") (pintype "bidirectional"))
    )
    (net (code "85") (name "unconnected-(U$1-SD_SCK-PadP$3)") (class "Default")
      (node (ref "U$1") (pin "P$3") (pinfunction "SD_SCK_P$3") (pintype "bidirectional"))
    )
    (net (code "86") (name "unconnected-(U$2-CTS-Pad9)") (class "Default")
      (node (ref "U$2") (pin "9") (pinfunction "CTS_9") (pintype "bidirectional"))
    )
    (net (code "87") (name "unconnected-(U$2-DCD-Pad12)") (class "Default")
      (node (ref "U$2") (pin "12") (pinfunction "DCD_12") (pintype "bidirectional"))
    )
    (net (code "88") (name "unconnected-(U$2-DSR-Pad10)") (class "Default")
      (node (ref "U$2") (pin "10") (pinfunction "DSR_10") (pintype "bidirectional"))
    )
    (net (code "89") (name "unconnected-(U$2-DTR-Pad13)") (class "Default")
      (node (ref "U$2") (pin "13") (pinfunction "DTR_13") (pintype "bidirectional"))
    )
    (net (code "90") (name "unconnected-(U$2-R232-Pad15)") (class "Default")
      (node (ref "U$2") (pin "15") (pinfunction "R232_15") (pintype "bidirectional"))
    )
    (net (code "91") (name "unconnected-(U$2-RI-Pad11)") (class "Default")
      (node (ref "U$2") (pin "11") (pinfunction "RI_11") (pintype "bidirectional"))
    )
  )
)
